# moire_v1_5-routed.net
KiCad netlist of a schematic drawn in EAGLE
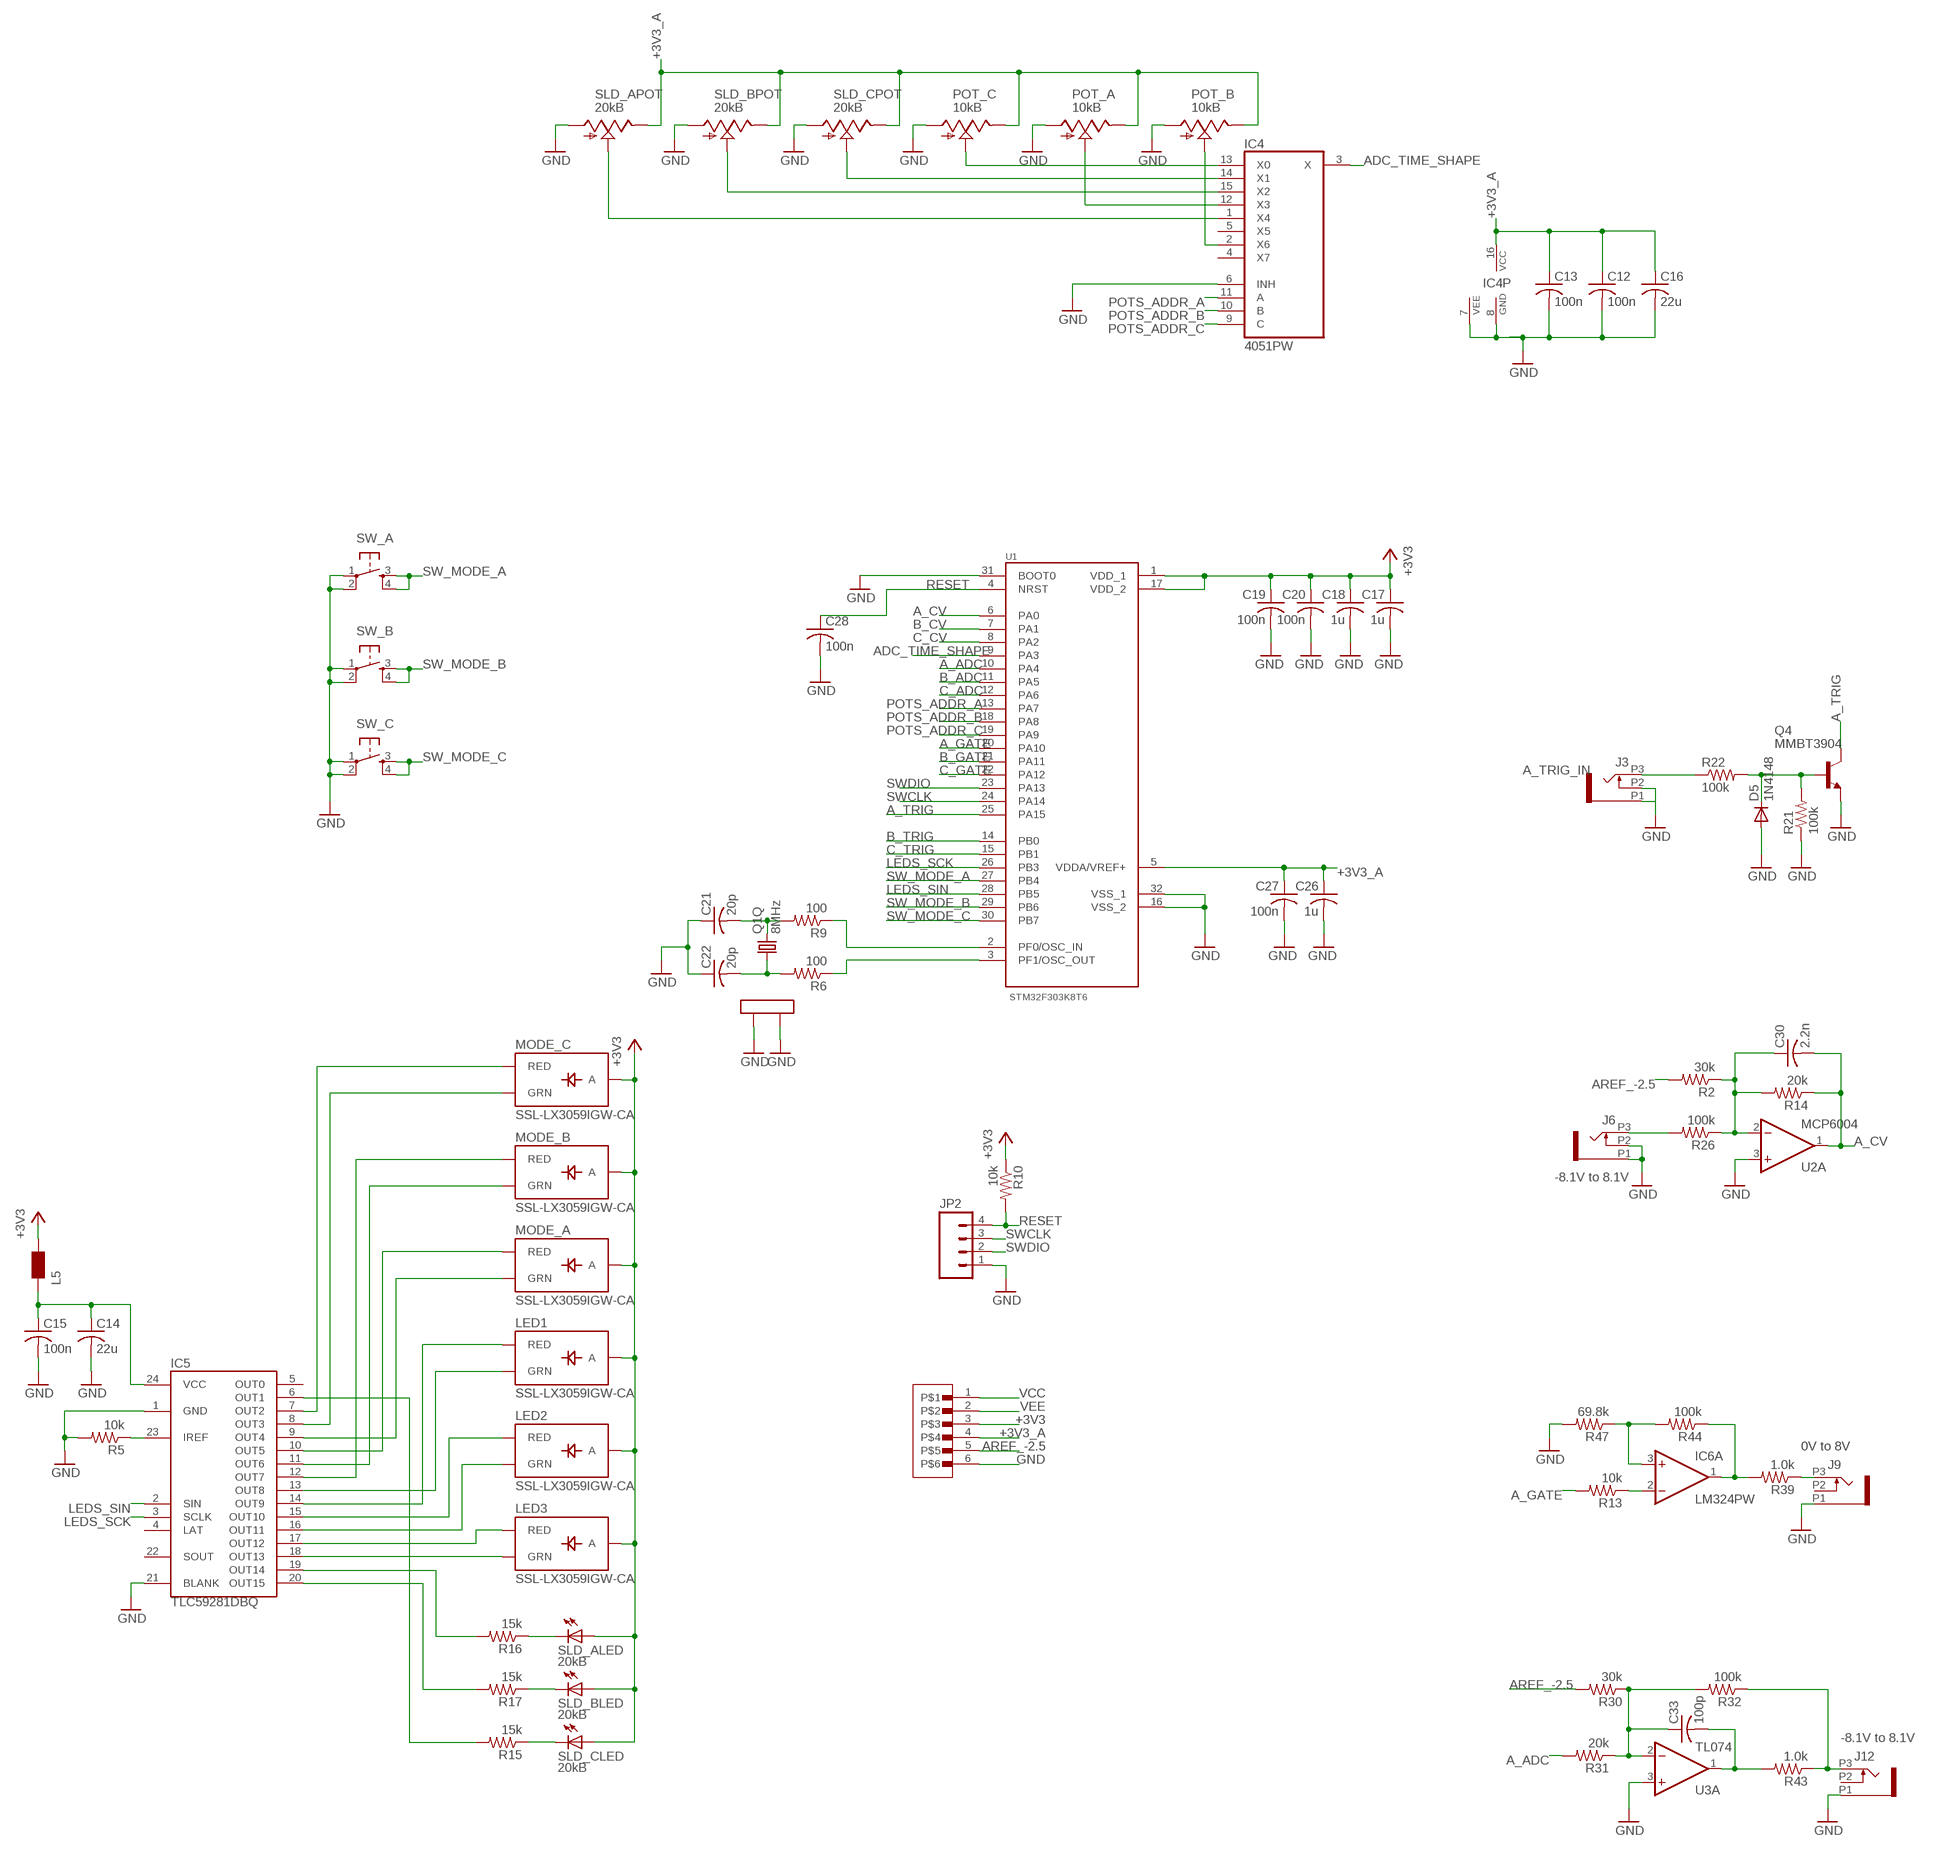
[diagram p0: schematic, sheet 1, part 1 of 2]
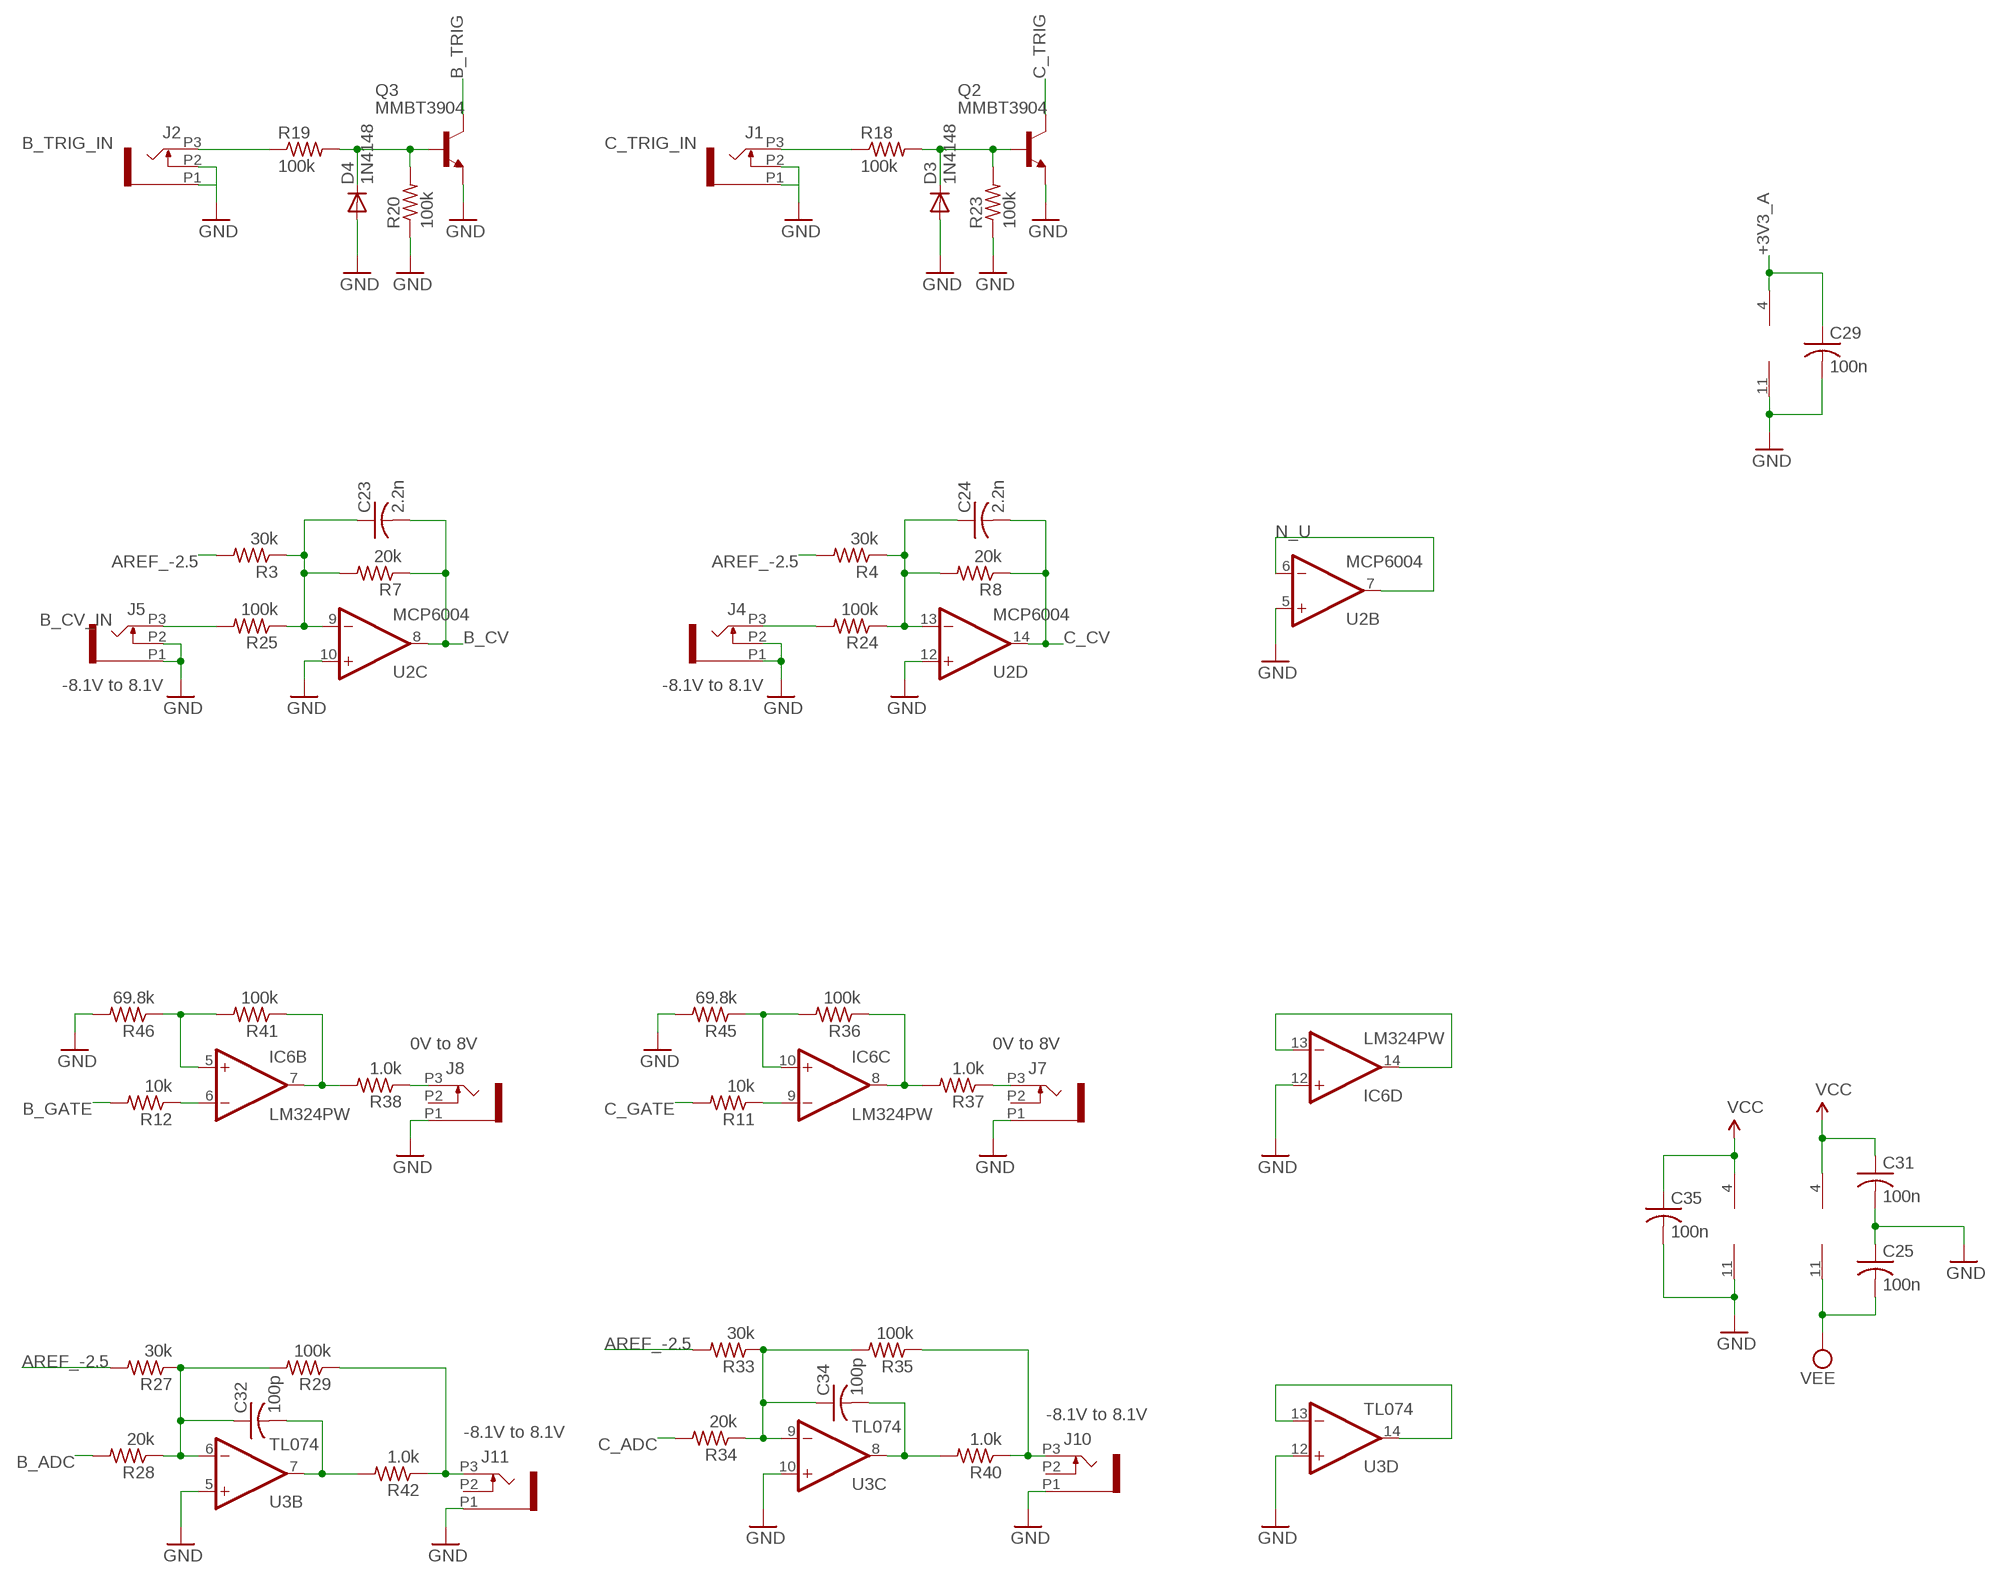
[diagram p1: schematic, sheet 1, part 2 of 2]
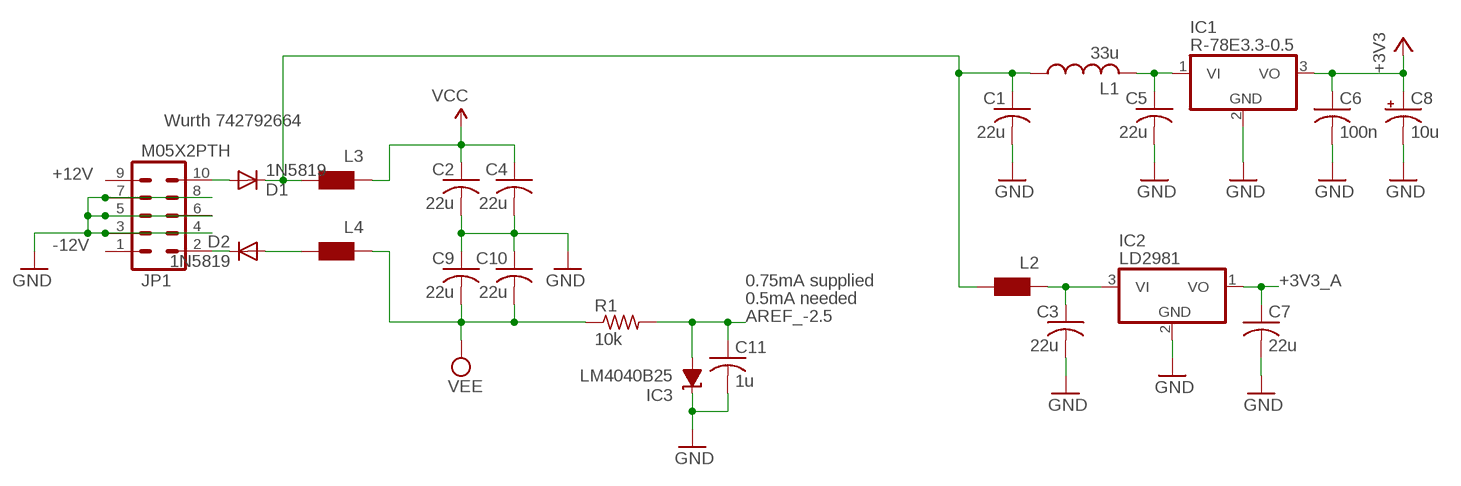
[diagram p2: schematic, sheet 2]

(export (version "E")
  (design (tool "Eeschema 10.0.6"))
  (components
    (comp (ref "C12")
      (value "100n")
      (footprint "eagle-import:C0603")
      (libsource (lib "eagle-import") (part "C-USC0603"))
    )
    (comp (ref "C13")
      (value "100n")
      (footprint "eagle-import:C0603")
      (libsource (lib "eagle-import") (part "C-USC0603"))
    )
    (comp (ref "C14")
      (value "22u")
      (footprint "eagle-import:C1206")
      (libsource (lib "eagle-import") (part "C-USC1206"))
    )
    (comp (ref "C15")
      (value "100n")
      (footprint "eagle-import:C0603")
      (libsource (lib "eagle-import") (part "C-USC0603"))
    )
    (comp (ref "C16")
      (value "22u")
      (footprint "eagle-import:C1206")
      (libsource (lib "eagle-import") (part "C-USC1206"))
    )
    (comp (ref "C17")
      (value "1u")
      (footprint "eagle-import:C0603")
      (libsource (lib "eagle-import") (part "C-USC0603"))
    )
    (comp (ref "C18")
      (value "1u")
      (footprint "eagle-import:C0603")
      (libsource (lib "eagle-import") (part "C-USC0603"))
    )
    (comp (ref "C19")
      (value "100n")
      (footprint "eagle-import:C0603")
      (libsource (lib "eagle-import") (part "C-USC0603"))
    )
    (comp (ref "C20")
      (value "100n")
      (footprint "eagle-import:C0603")
      (libsource (lib "eagle-import") (part "C-USC0603"))
    )
    (comp (ref "C21")
      (value "20p")
      (footprint "eagle-import:C0603")
      (libsource (lib "eagle-import") (part "C-USC0603"))
    )
    (comp (ref "C22")
      (value "20p")
      (footprint "eagle-import:C0603")
      (libsource (lib "eagle-import") (part "C-USC0603"))
    )
    (comp (ref "C23")
      (value "2.2n")
      (footprint "eagle-import:C0603")
      (libsource (lib "eagle-import") (part "C-USC0603"))
    )
    (comp (ref "C24")
      (value "2.2n")
      (footprint "eagle-import:C0603")
      (libsource (lib "eagle-import") (part "C-USC0603"))
    )
    (comp (ref "C25")
      (value "100n")
      (footprint "eagle-import:C0603")
      (libsource (lib "eagle-import") (part "C-USC0603"))
    )
    (comp (ref "C26")
      (value "1u")
      (footprint "eagle-import:C0603")
      (libsource (lib "eagle-import") (part "C-USC0603"))
    )
    (comp (ref "C27")
      (value "100n")
      (footprint "eagle-import:C0603")
      (libsource (lib "eagle-import") (part "C-USC0603"))
    )
    (comp (ref "C28")
      (value "100n")
      (footprint "eagle-import:C0603")
      (libsource (lib "eagle-import") (part "C-USC0603"))
    )
    (comp (ref "C29")
      (value "100n")
      (footprint "eagle-import:C0603")
      (libsource (lib "eagle-import") (part "C-USC0603"))
    )
    (comp (ref "C30")
      (value "2.2n")
      (footprint "eagle-import:C0603")
      (libsource (lib "eagle-import") (part "C-USC0603"))
    )
    (comp (ref "C31")
      (value "100n")
      (footprint "eagle-import:C0603")
      (libsource (lib "eagle-import") (part "C-USC0603"))
    )
    (comp (ref "C32")
      (value "100p")
      (footprint "eagle-import:C0603")
      (libsource (lib "eagle-import") (part "C-USC0603"))
    )
    (comp (ref "C33")
      (value "100p")
      (footprint "eagle-import:C0603")
      (libsource (lib "eagle-import") (part "C-USC0603"))
    )
    (comp (ref "C34")
      (value "100p")
      (footprint "eagle-import:C0603")
      (libsource (lib "eagle-import") (part "C-USC0603"))
    )
    (comp (ref "C35")
      (value "100n")
      (footprint "eagle-import:C0603")
      (libsource (lib "eagle-import") (part "C-USC0603"))
    )
    (comp (ref "D3")
      (value "1N4148")
      (footprint "eagle-import:SOD523")
      (libsource (lib "eagle-import") (part "DIODE-SOD523"))
    )
    (comp (ref "D4")
      (value "1N4148")
      (footprint "eagle-import:SOD523")
      (libsource (lib "eagle-import") (part "DIODE-SOD523"))
    )
    (comp (ref "D5")
      (value "1N4148")
      (footprint "eagle-import:SOD523")
      (libsource (lib "eagle-import") (part "DIODE-SOD523"))
    )
    (comp (ref "IC4")
      (value "4051PW")
      (footprint "eagle-import:TSSOP16_065")
      (libsource (lib "eagle-import") (part "4051PW"))
    )
    (comp (ref "IC5")
      (value "TLC59281DBQ")
      (footprint "eagle-import:TSSOP24_0635")
      (libsource (lib "eagle-import") (part "TLC59281DBQ"))
    )
    (comp (ref "IC6")
      (value "LM324PW")
      (footprint "eagle-import:TSSOP14_065")
      (libsource (lib "eagle-import") (part "TL074PW"))
    )
    (comp (ref "J1")
      (value "PJ301_THONKICONN6")
      (footprint "eagle-import:WQP_PJ_301M6")
      (libsource (lib "eagle-import") (part "PJ301_THONKICONN6"))
    )
    (comp (ref "J2")
      (value "PJ301_THONKICONN6")
      (footprint "eagle-import:WQP_PJ_301M6")
      (libsource (lib "eagle-import") (part "PJ301_THONKICONN6"))
    )
    (comp (ref "J3")
      (value "PJ301_THONKICONN6")
      (footprint "eagle-import:WQP_PJ_301M6")
      (libsource (lib "eagle-import") (part "PJ301_THONKICONN6"))
    )
    (comp (ref "J4")
      (value "PJ301_THONKICONN6")
      (footprint "eagle-import:WQP_PJ_301M6")
      (libsource (lib "eagle-import") (part "PJ301_THONKICONN6"))
    )
    (comp (ref "J5")
      (value "PJ301_THONKICONN6")
      (footprint "eagle-import:WQP_PJ_301M6")
      (libsource (lib "eagle-import") (part "PJ301_THONKICONN6"))
    )
    (comp (ref "J6")
      (value "PJ301_THONKICONN6")
      (footprint "eagle-import:WQP_PJ_301M6")
      (libsource (lib "eagle-import") (part "PJ301_THONKICONN6"))
    )
    (comp (ref "J7")
      (value "PJ301_THONKICONN6")
      (footprint "eagle-import:WQP_PJ_301M6")
      (libsource (lib "eagle-import") (part "PJ301_THONKICONN6"))
    )
    (comp (ref "J8")
      (value "PJ301_THONKICONN6")
      (footprint "eagle-import:WQP_PJ_301M6")
      (libsource (lib "eagle-import") (part "PJ301_THONKICONN6"))
    )
    (comp (ref "J9")
      (value "PJ301_THONKICONN6")
      (footprint "eagle-import:WQP_PJ_301M6")
      (libsource (lib "eagle-import") (part "PJ301_THONKICONN6"))
    )
    (comp (ref "J10")
      (value "PJ301_THONKICONN6")
      (footprint "eagle-import:WQP_PJ_301M6")
      (libsource (lib "eagle-import") (part "PJ301_THONKICONN6"))
    )
    (comp (ref "J11")
      (value "PJ301_THONKICONN6")
      (footprint "eagle-import:WQP_PJ_301M6")
      (libsource (lib "eagle-import") (part "PJ301_THONKICONN6"))
    )
    (comp (ref "J12")
      (value "PJ301_THONKICONN6")
      (footprint "eagle-import:WQP_PJ_301M6")
      (libsource (lib "eagle-import") (part "PJ301_THONKICONN6"))
    )
    (comp (ref "JP2")
      (value "M04PTH")
      (footprint "eagle-import:1X04")
      (libsource (lib "eagle-import") (part "M04PTH"))
    )
    (comp (ref "L5")
      (value "WE-CBF_0603")
      (footprint "eagle-import:0603")
      (libsource (lib "eagle-import") (part "WE-CBF_0603"))
    )
    (comp (ref "LED1")
      (value "SSL-LX3059IGW-CA")
      (footprint "eagle-import:LED-BICOLOR-THROUGHHOLE-LUMEX")
      (libsource (lib "eagle-import") (part "LED-BICOLOR-THROUGHHOLE-CA"))
    )
    (comp (ref "LED2")
      (value "SSL-LX3059IGW-CA")
      (footprint "eagle-import:LED-BICOLOR-THROUGHHOLE-LUMEX")
      (libsource (lib "eagle-import") (part "LED-BICOLOR-THROUGHHOLE-CA"))
    )
    (comp (ref "LED3")
      (value "SSL-LX3059IGW-CA")
      (footprint "eagle-import:LED-BICOLOR-THROUGHHOLE-LUMEX")
      (libsource (lib "eagle-import") (part "LED-BICOLOR-THROUGHHOLE-CA"))
    )
    (comp (ref "MODE_A")
      (value "SSL-LX3059IGW-CA")
      (footprint "eagle-import:LED-BICOLOR-THROUGHHOLE-LUMEX")
      (libsource (lib "eagle-import") (part "LED-BICOLOR-THROUGHHOLE-CA"))
    )
    (comp (ref "MODE_B")
      (value "SSL-LX3059IGW-CA")
      (footprint "eagle-import:LED-BICOLOR-THROUGHHOLE-LUMEX")
      (libsource (lib "eagle-import") (part "LED-BICOLOR-THROUGHHOLE-CA"))
    )
    (comp (ref "MODE_C")
      (value "SSL-LX3059IGW-CA")
      (footprint "eagle-import:LED-BICOLOR-THROUGHHOLE-LUMEX")
      (libsource (lib "eagle-import") (part "LED-BICOLOR-THROUGHHOLE-CA"))
    )
    (comp (ref "POT_A")
      (value "10kB")
      (footprint "eagle-import:ALPS_POT_VERTICAL")
      (libsource (lib "eagle-import") (part "POT_USVERTICAL"))
    )
    (comp (ref "POT_B")
      (value "10kB")
      (footprint "eagle-import:ALPS_POT_VERTICAL")
      (libsource (lib "eagle-import") (part "POT_USVERTICAL"))
    )
    (comp (ref "POT_C")
      (value "10kB")
      (footprint "eagle-import:ALPS_POT_VERTICAL")
      (libsource (lib "eagle-import") (part "POT_USVERTICAL"))
    )
    (comp (ref "Q1")
      (value "8MHz")
      (footprint "eagle-import:CTS406")
      (libsource (lib "eagle-import") (part "CRYSTAL"))
    )
    (comp (ref "Q2")
      (value "MMBT3904")
      (footprint "eagle-import:SOT23-BEC")
      (libsource (lib "eagle-import") (part "-NPN-SOT23-BECMMBT3904LT1"))
    )
    (comp (ref "Q3")
      (value "MMBT3904")
      (footprint "eagle-import:SOT23-BEC")
      (libsource (lib "eagle-import") (part "-NPN-SOT23-BECMMBT3904LT1"))
    )
    (comp (ref "Q4")
      (value "MMBT3904")
      (footprint "eagle-import:SOT23-BEC")
      (libsource (lib "eagle-import") (part "-NPN-SOT23-BECMMBT3904LT1"))
    )
    (comp (ref "R2")
      (value "30k")
      (footprint "eagle-import:R0603")
      (libsource (lib "eagle-import") (part "R-US_R0603"))
    )
    (comp (ref "R3")
      (value "30k")
      (footprint "eagle-import:R0603")
      (libsource (lib "eagle-import") (part "R-US_R0603"))
    )
    (comp (ref "R4")
      (value "30k")
      (footprint "eagle-import:R0603")
      (libsource (lib "eagle-import") (part "R-US_R0603"))
    )
    (comp (ref "R5")
      (value "10k")
      (footprint "eagle-import:R0603")
      (libsource (lib "eagle-import") (part "R-US_R0603"))
    )
    (comp (ref "R6")
      (value "100")
      (footprint "eagle-import:R0603")
      (libsource (lib "eagle-import") (part "R-US_R0603"))
    )
    (comp (ref "R7")
      (value "20k")
      (footprint "eagle-import:R0603")
      (libsource (lib "eagle-import") (part "R-US_R0603"))
    )
    (comp (ref "R8")
      (value "20k")
      (footprint "eagle-import:R0603")
      (libsource (lib "eagle-import") (part "R-US_R0603"))
    )
    (comp (ref "R9")
      (value "100")
      (footprint "eagle-import:R0603")
      (libsource (lib "eagle-import") (part "R-US_R0603"))
    )
    (comp (ref "R10")
      (value "10k")
      (footprint "eagle-import:R0603")
      (libsource (lib "eagle-import") (part "R-US_R0603"))
    )
    (comp (ref "R11")
      (value "10k")
      (footprint "eagle-import:R0603")
      (libsource (lib "eagle-import") (part "R-US_R0603"))
    )
    (comp (ref "R12")
      (value "10k")
      (footprint "eagle-import:R0603")
      (libsource (lib "eagle-import") (part "R-US_R0603"))
    )
    (comp (ref "R13")
      (value "10k")
      (footprint "eagle-import:R0603")
      (libsource (lib "eagle-import") (part "R-US_R0603"))
    )
    (comp (ref "R14")
      (value "20k")
      (footprint "eagle-import:R0603")
      (libsource (lib "eagle-import") (part "R-US_R0603"))
    )
    (comp (ref "R15")
      (value "15k")
      (footprint "eagle-import:R0603")
      (libsource (lib "eagle-import") (part "R-US_R0603"))
    )
    (comp (ref "R16")
      (value "15k")
      (footprint "eagle-import:R0603")
      (libsource (lib "eagle-import") (part "R-US_R0603"))
    )
    (comp (ref "R17")
      (value "15k")
      (footprint "eagle-import:R0603")
      (libsource (lib "eagle-import") (part "R-US_R0603"))
    )
    (comp (ref "R18")
      (value "100k")
      (footprint "eagle-import:R0603")
      (libsource (lib "eagle-import") (part "R-US_R0603"))
    )
    (comp (ref "R19")
      (value "100k")
      (footprint "eagle-import:R0603")
      (libsource (lib "eagle-import") (part "R-US_R0603"))
    )
    (comp (ref "R20")
      (value "100k")
      (footprint "eagle-import:R0603")
      (libsource (lib "eagle-import") (part "R-US_R0603"))
    )
    (comp (ref "R21")
      (value "100k")
      (footprint "eagle-import:R0603")
      (libsource (lib "eagle-import") (part "R-US_R0603"))
    )
    (comp (ref "R22")
      (value "100k")
      (footprint "eagle-import:R0603")
      (libsource (lib "eagle-import") (part "R-US_R0603"))
    )
    (comp (ref "R23")
      (value "100k")
      (footprint "eagle-import:R0603")
      (libsource (lib "eagle-import") (part "R-US_R0603"))
    )
    (comp (ref "R24")
      (value "100k")
      (footprint "eagle-import:R0603")
      (libsource (lib "eagle-import") (part "R-US_R0603"))
    )
    (comp (ref "R25")
      (value "100k")
      (footprint "eagle-import:R0603")
      (libsource (lib "eagle-import") (part "R-US_R0603"))
    )
    (comp (ref "R26")
      (value "100k")
      (footprint "eagle-import:R0603")
      (libsource (lib "eagle-import") (part "R-US_R0603"))
    )
    (comp (ref "R27")
      (value "30k")
      (footprint "eagle-import:R0603")
      (libsource (lib "eagle-import") (part "R-US_R0603"))
    )
    (comp (ref "R28")
      (value "20k")
      (footprint "eagle-import:R0603")
      (libsource (lib "eagle-import") (part "R-US_R0603"))
    )
    (comp (ref "R29")
      (value "100k")
      (footprint "eagle-import:R0603")
      (libsource (lib "eagle-import") (part "R-US_R0603"))
    )
    (comp (ref "R30")
      (value "30k")
      (footprint "eagle-import:R0603")
      (libsource (lib "eagle-import") (part "R-US_R0603"))
    )
    (comp (ref "R31")
      (value "20k")
      (footprint "eagle-import:R0603")
      (libsource (lib "eagle-import") (part "R-US_R0603"))
    )
    (comp (ref "R32")
      (value "100k")
      (footprint "eagle-import:R0603")
      (libsource (lib "eagle-import") (part "R-US_R0603"))
    )
    (comp (ref "R33")
      (value "30k")
      (footprint "eagle-import:R0603")
      (libsource (lib "eagle-import") (part "R-US_R0603"))
    )
    (comp (ref "R34")
      (value "20k")
      (footprint "eagle-import:R0603")
      (libsource (lib "eagle-import") (part "R-US_R0603"))
    )
    (comp (ref "R35")
      (value "100k")
      (footprint "eagle-import:R0603")
      (libsource (lib "eagle-import") (part "R-US_R0603"))
    )
    (comp (ref "R36")
      (value "100k")
      (footprint "eagle-import:R0603")
      (libsource (lib "eagle-import") (part "R-US_R0603"))
    )
    (comp (ref "R37")
      (value "1.0k")
      (footprint "eagle-import:R0603")
      (libsource (lib "eagle-import") (part "R-US_R0603"))
    )
    (comp (ref "R38")
      (value "1.0k")
      (footprint "eagle-import:R0603")
      (libsource (lib "eagle-import") (part "R-US_R0603"))
    )
    (comp (ref "R39")
      (value "1.0k")
      (footprint "eagle-import:R0603")
      (libsource (lib "eagle-import") (part "R-US_R0603"))
    )
    (comp (ref "R40")
      (value "1.0k")
      (footprint "eagle-import:R0603")
      (libsource (lib "eagle-import") (part "R-US_R0603"))
    )
    (comp (ref "R41")
      (value "100k")
      (footprint "eagle-import:R0603")
      (libsource (lib "eagle-import") (part "R-US_R0603"))
    )
    (comp (ref "R42")
      (value "1.0k")
      (footprint "eagle-import:R0603")
      (libsource (lib "eagle-import") (part "R-US_R0603"))
    )
    (comp (ref "R43")
      (value "1.0k")
      (footprint "eagle-import:R0603")
      (libsource (lib "eagle-import") (part "R-US_R0603"))
    )
    (comp (ref "R44")
      (value "100k")
      (footprint "eagle-import:R0603")
      (libsource (lib "eagle-import") (part "R-US_R0603"))
    )
    (comp (ref "R45")
      (value "69.8k")
      (footprint "eagle-import:R0603")
      (libsource (lib "eagle-import") (part "R-US_R0603"))
    )
    (comp (ref "R46")
      (value "69.8k")
      (footprint "eagle-import:R0603")
      (libsource (lib "eagle-import") (part "R-US_R0603"))
    )
    (comp (ref "R47")
      (value "69.8k")
      (footprint "eagle-import:R0603")
      (libsource (lib "eagle-import") (part "R-US_R0603"))
    )
    (comp (ref "SLD_A")
      (value "20kB")
      (footprint "eagle-import:BOURNS_SLIDER")
      (libsource (lib "eagle-import") (part "BOURNS_SLIDER"))
    )
    (comp (ref "SLD_B")
      (value "20kB")
      (footprint "eagle-import:BOURNS_SLIDER")
      (libsource (lib "eagle-import") (part "BOURNS_SLIDER"))
    )
    (comp (ref "SLD_C")
      (value "20kB")
      (footprint "eagle-import:BOURNS_SLIDER")
      (libsource (lib "eagle-import") (part "BOURNS_SLIDER"))
    )
    (comp (ref "SW_A")
      (value "TAC_SWITCHPTH")
      (footprint "eagle-import:TACTILE-PTH")
      (libsource (lib "eagle-import") (part "TAC_SWITCHPTH"))
    )
    (comp (ref "SW_B")
      (value "TAC_SWITCHPTH")
      (footprint "eagle-import:TACTILE-PTH")
      (libsource (lib "eagle-import") (part "TAC_SWITCHPTH"))
    )
    (comp (ref "SW_C")
      (value "TAC_SWITCHPTH")
      (footprint "eagle-import:TACTILE-PTH")
      (libsource (lib "eagle-import") (part "TAC_SWITCHPTH"))
    )
    (comp (ref "U$1")
      (value "1X6-SMD-TESTPAD")
      (footprint "eagle-import:6X1-SMD-TESTPAD")
      (libsource (lib "eagle-import") (part "1X6-SMD-TESTPAD"))
    )
    (comp (ref "U1")
      (value "STM32F303K8T6")
      (footprint "eagle-import:QFP80P900X900X160-32N")
      (fields (field (name "MF") "STMicroelectronics"))
      (libsource (lib "eagle-import") (part "STM32F303K8T6"))
    )
    (comp (ref "U2")
      (value "MCP6004")
      (footprint "eagle-import:SO14")
      (libsource (lib "eagle-import") (part "MCP6004_SMD"))
    )
    (comp (ref "U3")
      (value "TL074")
      (footprint "eagle-import:SO14")
      (libsource (lib "eagle-import") (part "TL074_SMD"))
    )
    (comp (ref "C1")
      (value "22u")
      (footprint "eagle-import:C1206")
      (libsource (lib "eagle-import") (part "C-USC1206"))
    )
    (comp (ref "C2")
      (value "22u")
      (footprint "eagle-import:C1206")
      (libsource (lib "eagle-import") (part "C-USC1206"))
    )
    (comp (ref "C3")
      (value "22u")
      (footprint "eagle-import:C1206")
      (libsource (lib "eagle-import") (part "C-USC1206"))
    )
    (comp (ref "C4")
      (value "22u")
      (footprint "eagle-import:C1206")
      (libsource (lib "eagle-import") (part "C-USC1206"))
    )
    (comp (ref "C5")
      (value "22u")
      (footprint "eagle-import:C1206")
      (libsource (lib "eagle-import") (part "C-USC1206"))
    )
    (comp (ref "C6")
      (value "100n")
      (footprint "eagle-import:C0603")
      (libsource (lib "eagle-import") (part "C-USC0603"))
    )
    (comp (ref "C7")
      (value "22u")
      (footprint "eagle-import:C1206")
      (libsource (lib "eagle-import") (part "C-USC1206"))
    )
    (comp (ref "C8")
      (value "10u")
      (footprint "eagle-import:PANASONIC_A")
      (libsource (lib "eagle-import") (part "CPOL-USA"))
    )
    (comp (ref "C9")
      (value "22u")
      (footprint "eagle-import:C1206")
      (libsource (lib "eagle-import") (part "C-USC1206"))
    )
    (comp (ref "C10")
      (value "22u")
      (footprint "eagle-import:C1206")
      (libsource (lib "eagle-import") (part "C-USC1206"))
    )
    (comp (ref "C11")
      (value "1u")
      (footprint "eagle-import:C0603")
      (libsource (lib "eagle-import") (part "C-USC0603"))
    )
    (comp (ref "D1")
      (value "1N5819")
      (footprint "eagle-import:SOD123")
      (libsource (lib "eagle-import") (part "DIODE-SOD123"))
    )
    (comp (ref "D2")
      (value "1N5819")
      (footprint "eagle-import:SOD123")
      (libsource (lib "eagle-import") (part "DIODE-SOD123"))
    )
    (comp (ref "IC1")
      (value "R-78E3.3-0.5")
      (footprint "eagle-import:WE78")
      (libsource (lib "eagle-import") (part "WE173950378"))
    )
    (comp (ref "IC2")
      (value "LD2981")
      (footprint "eagle-import:SOT89")
      (libsource (lib "eagle-import") (part "LD2981ABU"))
    )
    (comp (ref "IC3")
      (value "LM4040B25")
      (footprint "eagle-import:DBZ_R-PDSO-G3")
      (libsource (lib "eagle-import") (part "LM4041DBZB12"))
    )
    (comp (ref "JP1")
      (value "M05X2PTH")
      (footprint "eagle-import:2X5-PTH")
      (libsource (lib "eagle-import") (part "M05X2PTH"))
    )
    (comp (ref "L1")
      (value "33u")
      (footprint "eagle-import:L2012C")
      (libsource (lib "eagle-import") (part "L-USL2012C"))
    )
    (comp (ref "L2")
      (value "WE-CBF_0603")
      (footprint "eagle-import:0603")
      (libsource (lib "eagle-import") (part "WE-CBF_0603"))
    )
    (comp (ref "L3")
      (value "WE-CBF_0603")
      (footprint "eagle-import:0603")
      (libsource (lib "eagle-import") (part "WE-CBF_0603"))
    )
    (comp (ref "L4")
      (value "WE-CBF_0603")
      (footprint "eagle-import:0603")
      (libsource (lib "eagle-import") (part "WE-CBF_0603"))
    )
    (comp (ref "R1")
      (value "10k")
      (footprint "eagle-import:R0603")
      (libsource (lib "eagle-import") (part "R-US_R0603"))
    )
  )
  (nets
    (net (code "1") (name "+3V3") (class "Default")
      (node (ref "C17") (pin "1") (pinfunction "1_1") (pintype "passive"))
      (node (ref "C18") (pin "1") (pinfunction "1_1") (pintype "passive"))
      (node (ref "C19") (pin "1") (pinfunction "1_1") (pintype "passive"))
      (node (ref "C20") (pin "1") (pinfunction "1_1") (pintype "passive"))
      (node (ref "C6") (pin "1") (pinfunction "1_1") (pintype "passive"))
      (node (ref "C8") (pin "+") (pinfunction "+_+") (pintype "passive"))
      (node (ref "IC1") (pin "3") (pinfunction "VO_3") (pintype "passive"))
      (node (ref "L5") (pin "2") (pinfunction "2_2") (pintype "passive"))
      (node (ref "LED1") (pin "A") (pinfunction "A_A") (pintype "bidirectional"))
      (node (ref "LED2") (pin "A") (pinfunction "A_A") (pintype "bidirectional"))
      (node (ref "LED3") (pin "A") (pinfunction "A_A") (pintype "bidirectional"))
      (node (ref "MODE_A") (pin "A") (pinfunction "A_A") (pintype "bidirectional"))
      (node (ref "MODE_B") (pin "A") (pinfunction "A_A") (pintype "bidirectional"))
      (node (ref "MODE_C") (pin "A") (pinfunction "A_A") (pintype "bidirectional"))
      (node (ref "R10") (pin "1") (pinfunction "1_1") (pintype "passive"))
      (node (ref "SLD_A") (pin "B") (pinfunction "A_B") (pintype "passive"))
      (node (ref "SLD_B") (pin "B") (pinfunction "A_B") (pintype "passive"))
      (node (ref "SLD_C") (pin "B") (pinfunction "A_B") (pintype "passive"))
      (node (ref "U$1") (pin "3") (pinfunction "P$3_3") (pintype "bidirectional"))
      (node (ref "U1") (pin "1") (pinfunction "VDD_1_1") (pintype "power_in"))
      (node (ref "U1") (pin "17") (pinfunction "VDD_2_17") (pintype "power_in"))
    )
    (net (code "2") (name "+3V3_A") (class "Default")
      (node (ref "C12") (pin "1") (pinfunction "1_1") (pintype "passive"))
      (node (ref "C13") (pin "1") (pinfunction "1_1") (pintype "passive"))
      (node (ref "C16") (pin "1") (pinfunction "1_1") (pintype "passive"))
      (node (ref "C26") (pin "1") (pinfunction "1_1") (pintype "passive"))
      (node (ref "C27") (pin "1") (pinfunction "1_1") (pintype "passive"))
      (node (ref "C29") (pin "1") (pinfunction "1_1") (pintype "passive"))
      (node (ref "C7") (pin "1") (pinfunction "1_1") (pintype "passive"))
      (node (ref "IC2") (pin "1") (pinfunction "VO_1") (pintype "passive"))
      (node (ref "IC4") (pin "16") (pinfunction "VCC_16") (pintype "power_in"))
      (node (ref "POT_A") (pin "P$1") (pinfunction "E_P$1") (pintype "passive"))
      (node (ref "POT_B") (pin "P$1") (pinfunction "E_P$1") (pintype "passive"))
      (node (ref "POT_C") (pin "P$1") (pinfunction "E_P$1") (pintype "passive"))
      (node (ref "SLD_A") (pin "3") (pinfunction "E_3") (pintype "passive"))
      (node (ref "SLD_B") (pin "3") (pinfunction "E_3") (pintype "passive"))
      (node (ref "SLD_C") (pin "3") (pinfunction "E_3") (pintype "passive"))
      (node (ref "U$1") (pin "4") (pinfunction "P$4_4") (pintype "bidirectional"))
      (node (ref "U1") (pin "5") (pinfunction "VDDA/VREF+_5") (pintype "power_in"))
      (node (ref "U2") (pin "4") (pinfunction "V+_4") (pintype "power_in"))
    )
    (net (code "3") (name "+12V") (class "Default")
      (node (ref "D1") (pin "A") (pinfunction "A_A") (pintype "passive"))
      (node (ref "JP1") (pin "10") (pinfunction "10_10") (pintype "passive"))
      (node (ref "JP1") (pin "9") (pinfunction "9_9") (pintype "passive"))
    )
    (net (code "4") (name "-12V") (class "Default")
      (node (ref "D2") (pin "C") (pinfunction "C_C") (pintype "passive"))
      (node (ref "JP1") (pin "1") (pinfunction "1_1") (pintype "passive"))
      (node (ref "JP1") (pin "2") (pinfunction "2_2") (pintype "passive"))
    )
    (net (code "5") (name "ADC_TIME_SHAPE") (class "Default")
      (node (ref "IC4") (pin "3") (pinfunction "X_3") (pintype "bidirectional"))
      (node (ref "U1") (pin "9") (pinfunction "PA3_9") (pintype "bidirectional"))
    )
    (net (code "6") (name "AREF_-2.5") (class "Default")
      (node (ref "C11") (pin "1") (pinfunction "1_1") (pintype "passive"))
      (node (ref "IC3") (pin "2") (pinfunction "A_2") (pintype "passive"))
      (node (ref "R1") (pin "2") (pinfunction "2_2") (pintype "passive"))
      (node (ref "R2") (pin "2") (pinfunction "2_2") (pintype "passive"))
      (node (ref "R27") (pin "2") (pinfunction "2_2") (pintype "passive"))
      (node (ref "R3") (pin "2") (pinfunction "2_2") (pintype "passive"))
      (node (ref "R30") (pin "2") (pinfunction "2_2") (pintype "passive"))
      (node (ref "R33") (pin "2") (pinfunction "2_2") (pintype "passive"))
      (node (ref "R4") (pin "2") (pinfunction "2_2") (pintype "passive"))
      (node (ref "U$1") (pin "5") (pinfunction "P$5_5") (pintype "bidirectional"))
    )
    (net (code "7") (name "A_ADC") (class "Default")
      (node (ref "R31") (pin "2") (pinfunction "2_2") (pintype "passive"))
      (node (ref "U1") (pin "10") (pinfunction "PA4_10") (pintype "bidirectional"))
    )
    (net (code "8") (name "A_CV") (class "Default")
      (node (ref "C30") (pin "2") (pinfunction "2_2") (pintype "passive"))
      (node (ref "R14") (pin "1") (pinfunction "1_1") (pintype "passive"))
      (node (ref "U1") (pin "6") (pinfunction "PA0_6") (pintype "bidirectional"))
      (node (ref "U2") (pin "1") (pinfunction "OUT_1") (pintype "output"))
    )
    (net (code "9") (name "A_GATE") (class "Default")
      (node (ref "R13") (pin "2") (pinfunction "2_2") (pintype "passive"))
      (node (ref "U1") (pin "20") (pinfunction "PA10_20") (pintype "bidirectional"))
    )
    (net (code "10") (name "A_TRIG") (class "Default")
      (node (ref "Q4") (pin "C") (pinfunction "C_C") (pintype "passive"))
      (node (ref "U1") (pin "25") (pinfunction "PA15_25") (pintype "bidirectional"))
    )
    (net (code "11") (name "A_TRIG_IN") (class "Default")
      (node (ref "J3") (pin "P3") (pinfunction "3_P3") (pintype "passive"))
      (node (ref "R22") (pin "1") (pinfunction "1_1") (pintype "passive"))
    )
    (net (code "12") (name "B_ADC") (class "Default")
      (node (ref "R28") (pin "2") (pinfunction "2_2") (pintype "passive"))
      (node (ref "U1") (pin "11") (pinfunction "PA5_11") (pintype "bidirectional"))
    )
    (net (code "13") (name "B_CV") (class "Default")
      (node (ref "C23") (pin "2") (pinfunction "2_2") (pintype "passive"))
      (node (ref "R7") (pin "1") (pinfunction "1_1") (pintype "passive"))
      (node (ref "U1") (pin "7") (pinfunction "PA1_7") (pintype "bidirectional"))
      (node (ref "U2") (pin "8") (pinfunction "OUT_8") (pintype "output"))
    )
    (net (code "14") (name "B_CV_IN") (class "Default")
      (node (ref "J5") (pin "P3") (pinfunction "3_P3") (pintype "passive"))
      (node (ref "R25") (pin "2") (pinfunction "2_2") (pintype "passive"))
    )
    (net (code "15") (name "B_GATE") (class "Default")
      (node (ref "R12") (pin "2") (pinfunction "2_2") (pintype "passive"))
      (node (ref "U1") (pin "21") (pinfunction "PA11_21") (pintype "bidirectional"))
    )
    (net (code "16") (name "B_TRIG") (class "Default")
      (node (ref "Q3") (pin "C") (pinfunction "C_C") (pintype "passive"))
      (node (ref "U1") (pin "14") (pinfunction "PB0_14") (pintype "bidirectional"))
    )
    (net (code "17") (name "B_TRIG_IN") (class "Default")
      (node (ref "J2") (pin "P3") (pinfunction "3_P3") (pintype "passive"))
      (node (ref "R19") (pin "1") (pinfunction "1_1") (pintype "passive"))
    )
    (net (code "18") (name "C_ADC") (class "Default")
      (node (ref "R34") (pin "2") (pinfunction "2_2") (pintype "passive"))
      (node (ref "U1") (pin "12") (pinfunction "PA6_12") (pintype "bidirectional"))
    )
    (net (code "19") (name "C_CV") (class "Default")
      (node (ref "C24") (pin "2") (pinfunction "2_2") (pintype "passive"))
      (node (ref "R8") (pin "1") (pinfunction "1_1") (pintype "passive"))
      (node (ref "U1") (pin "8") (pinfunction "PA2_8") (pintype "bidirectional"))
      (node (ref "U2") (pin "14") (pinfunction "OUT_14") (pintype "output"))
    )
    (net (code "20") (name "C_GATE") (class "Default")
      (node (ref "R11") (pin "2") (pinfunction "2_2") (pintype "passive"))
      (node (ref "U1") (pin "22") (pinfunction "PA12_22") (pintype "bidirectional"))
    )
    (net (code "21") (name "C_TRIG") (class "Default")
      (node (ref "Q2") (pin "C") (pinfunction "C_C") (pintype "passive"))
      (node (ref "U1") (pin "15") (pinfunction "PB1_15") (pintype "bidirectional"))
    )
    (net (code "22") (name "C_TRIG_IN") (class "Default")
      (node (ref "J1") (pin "P3") (pinfunction "3_P3") (pintype "passive"))
      (node (ref "R18") (pin "1") (pinfunction "1_1") (pintype "passive"))
    )
    (net (code "23") (name "GND") (class "Default")
      (node (ref "C1") (pin "2") (pinfunction "2_2") (pintype "passive"))
      (node (ref "C10") (pin "1") (pinfunction "1_1") (pintype "passive"))
      (node (ref "C11") (pin "2") (pinfunction "2_2") (pintype "passive"))
      (node (ref "C12") (pin "2") (pinfunction "2_2") (pintype "passive"))
      (node (ref "C13") (pin "2") (pinfunction "2_2") (pintype "passive"))
      (node (ref "C14") (pin "2") (pinfunction "2_2") (pintype "passive"))
      (node (ref "C15") (pin "2") (pinfunction "2_2") (pintype "passive"))
      (node (ref "C16") (pin "2") (pinfunction "2_2") (pintype "passive"))
      (node (ref "C17") (pin "2") (pinfunction "2_2") (pintype "passive"))
      (node (ref "C18") (pin "2") (pinfunction "2_2") (pintype "passive"))
      (node (ref "C19") (pin "2") (pinfunction "2_2") (pintype "passive"))
      (node (ref "C2") (pin "2") (pinfunction "2_2") (pintype "passive"))
      (node (ref "C20") (pin "2") (pinfunction "2_2") (pintype "passive"))
      (node (ref "C21") (pin "1") (pinfunction "1_1") (pintype "passive"))
      (node (ref "C22") (pin "1") (pinfunction "1_1") (pintype "passive"))
      (node (ref "C25") (pin "1") (pinfunction "1_1") (pintype "passive"))
      (node (ref "C26") (pin "2") (pinfunction "2_2") (pintype "passive"))
      (node (ref "C27") (pin "2") (pinfunction "2_2") (pintype "passive"))
      (node (ref "C28") (pin "2") (pinfunction "2_2") (pintype "passive"))
      (node (ref "C29") (pin "2") (pinfunction "2_2") (pintype "passive"))
      (node (ref "C3") (pin "2") (pinfunction "2_2") (pintype "passive"))
      (node (ref "C31") (pin "2") (pinfunction "2_2") (pintype "passive"))
      (node (ref "C35") (pin "2") (pinfunction "2_2") (pintype "passive"))
      (node (ref "C4") (pin "2") (pinfunction "2_2") (pintype "passive"))
      (node (ref "C5") (pin "2") (pinfunction "2_2") (pintype "passive"))
      (node (ref "C6") (pin "2") (pinfunction "2_2") (pintype "passive"))
      (node (ref "C7") (pin "2") (pinfunction "2_2") (pintype "passive"))
      (node (ref "C8") (pin "-") (pinfunction "-_-") (pintype "passive"))
      (node (ref "C9") (pin "1") (pinfunction "1_1") (pintype "passive"))
      (node (ref "D3") (pin "A") (pinfunction "A_A") (pintype "passive"))
      (node (ref "D4") (pin "A") (pinfunction "A_A") (pintype "passive"))
      (node (ref "D5") (pin "A") (pinfunction "A_A") (pintype "passive"))
      (node (ref "IC1") (pin "2") (pinfunction "GND_2") (pintype "passive"))
      (node (ref "IC2") (pin "2") (pinfunction "GND_2") (pintype "passive"))
      (node (ref "IC3") (pin "1") (pinfunction "C_1") (pintype "passive"))
      (node (ref "IC4") (pin "6") (pinfunction "INH_6") (pintype "input"))
      (node (ref "IC4") (pin "7") (pinfunction "VEE_7") (pintype "power_in"))
      (node (ref "IC4") (pin "8") (pinfunction "GND_8") (pintype "power_in"))
      (node (ref "IC5") (pin "1") (pinfunction "GND_1") (pintype "bidirectional"))
      (node (ref "IC5") (pin "21") (pinfunction "BLANK_21") (pintype "bidirectional"))
      (node (ref "IC6") (pin "11") (pinfunction "V-_11") (pintype "power_in"))
      (node (ref "IC6") (pin "12") (pinfunction "+IN_12") (pintype "input"))
      (node (ref "J1") (pin "P1") (pinfunction "1_P1") (pintype "passive"))
      (node (ref "J1") (pin "P2") (pinfunction "2_P2") (pintype "passive"))
      (node (ref "J10") (pin "P1") (pinfunction "1_P1") (pintype "passive"))
      (node (ref "J11") (pin "P1") (pinfunction "1_P1") (pintype "passive"))
      (node (ref "J12") (pin "P1") (pinfunction "1_P1") (pintype "passive"))
      (node (ref "J2") (pin "P1") (pinfunction "1_P1") (pintype "passive"))
      (node (ref "J2") (pin "P2") (pinfunction "2_P2") (pintype "passive"))
      (node (ref "J3") (pin "P1") (pinfunction "1_P1") (pintype "passive"))
      (node (ref "J3") (pin "P2") (pinfunction "2_P2") (pintype "passive"))
      (node (ref "J4") (pin "P1") (pinfunction "1_P1") (pintype "passive"))
      (node (ref "J4") (pin "P2") (pinfunction "2_P2") (pintype "passive"))
      (node (ref "J5") (pin "P1") (pinfunction "1_P1") (pintype "passive"))
      (node (ref "J5") (pin "P2") (pinfunction "2_P2") (pintype "passive"))
      (node (ref "J6") (pin "P1") (pinfunction "1_P1") (pintype "passive"))
      (node (ref "J6") (pin "P2") (pinfunction "2_P2") (pintype "passive"))
      (node (ref "J7") (pin "P1") (pinfunction "1_P1") (pintype "passive"))
      (node (ref "J8") (pin "P1") (pinfunction "1_P1") (pintype "passive"))
      (node (ref "J9") (pin "P1") (pinfunction "1_P1") (pintype "passive"))
      (node (ref "JP1") (pin "3") (pinfunction "3_3") (pintype "passive"))
      (node (ref "JP1") (pin "4") (pinfunction "4_4") (pintype "passive"))
      (node (ref "JP1") (pin "5") (pinfunction "5_5") (pintype "passive"))
      (node (ref "JP1") (pin "6") (pinfunction "6_6") (pintype "passive"))
      (node (ref "JP1") (pin "7") (pinfunction "7_7") (pintype "passive"))
      (node (ref "JP1") (pin "8") (pinfunction "8_8") (pintype "passive"))
      (node (ref "JP2") (pin "1") (pinfunction "1_1") (pintype "passive"))
      (node (ref "POT_A") (pin "P$3") (pinfunction "A_P$3") (pintype "passive"))
      (node (ref "POT_B") (pin "P$3") (pinfunction "A_P$3") (pintype "passive"))
      (node (ref "POT_C") (pin "P$3") (pinfunction "A_P$3") (pintype "passive"))
      (node (ref "Q1") (pin "2") (pinfunction "LID1_2") (pintype "power_in"))
      (node (ref "Q1") (pin "4") (pinfunction "LID2_4") (pintype "power_in"))
      (node (ref "Q2") (pin "E") (pinfunction "E_E") (pintype "passive"))
      (node (ref "Q3") (pin "E") (pinfunction "E_E") (pintype "passive"))
      (node (ref "Q4") (pin "E") (pinfunction "E_E") (pintype "passive"))
      (node (ref "R20") (pin "1") (pinfunction "1_1") (pintype "passive"))
      (node (ref "R21") (pin "1") (pinfunction "1_1") (pintype "passive"))
      (node (ref "R23") (pin "1") (pinfunction "1_1") (pintype "passive"))
      (node (ref "R45") (pin "2") (pinfunction "2_2") (pintype "passive"))
      (node (ref "R46") (pin "2") (pinfunction "2_2") (pintype "passive"))
      (node (ref "R47") (pin "2") (pinfunction "2_2") (pintype "passive"))
      (node (ref "R5") (pin "2") (pinfunction "2_2") (pintype "passive"))
      (node (ref "SLD_A") (pin "1") (pinfunction "A_1") (pintype "passive"))
      (node (ref "SLD_B") (pin "1") (pinfunction "A_1") (pintype "passive"))
      (node (ref "SLD_C") (pin "1") (pinfunction "A_1") (pintype "passive"))
      (node (ref "SW_A") (pin "1") (pinfunction "1_1") (pintype "passive"))
      (node (ref "SW_A") (pin "2") (pinfunction "2_2") (pintype "passive"))
      (node (ref "SW_B") (pin "1") (pinfunction "1_1") (pintype "passive"))
      (node (ref "SW_B") (pin "2") (pinfunction "2_2") (pintype "passive"))
      (node (ref "SW_C") (pin "1") (pinfunction "1_1") (pintype "passive"))
      (node (ref "SW_C") (pin "2") (pinfunction "2_2") (pintype "passive"))
      (node (ref "U$1") (pin "6") (pinfunction "P$6_6") (pintype "bidirectional"))
      (node (ref "U1") (pin "16") (pinfunction "VSS_2_16") (pintype "power_in"))
      (node (ref "U1") (pin "31") (pinfunction "BOOT0_31") (pintype "input"))
      (node (ref "U1") (pin "32") (pinfunction "VSS_1_32") (pintype "power_in"))
      (node (ref "U2") (pin "10") (pinfunction "+IN_10") (pintype "input"))
      (node (ref "U2") (pin "11") (pinfunction "V-_11") (pintype "power_in"))
      (node (ref "U2") (pin "12") (pinfunction "+IN_12") (pintype "input"))
      (node (ref "U2") (pin "3") (pinfunction "+IN_3") (pintype "input"))
      (node (ref "U2") (pin "5") (pinfunction "+IN_5") (pintype "input"))
      (node (ref "U3") (pin "10") (pinfunction "+IN_10") (pintype "input"))
      (node (ref "U3") (pin "12") (pinfunction "+IN_12") (pintype "input"))
      (node (ref "U3") (pin "3") (pinfunction "+IN_3") (pintype "input"))
      (node (ref "U3") (pin "5") (pinfunction "+IN_5") (pintype "input"))
    )
    (net (code "24") (name "LEDS_SCK") (class "Default")
      (node (ref "IC5") (pin "3") (pinfunction "SCLK_3") (pintype "bidirectional"))
      (node (ref "U1") (pin "26") (pinfunction "PB3_26") (pintype "bidirectional"))
    )
    (net (code "25") (name "LEDS_SIN") (class "Default")
      (node (ref "IC5") (pin "2") (pinfunction "SIN_2") (pintype "bidirectional"))
      (node (ref "U1") (pin "28") (pinfunction "PB5_28") (pintype "bidirectional"))
    )
    (net (code "26") (name "N_U") (class "Default")
      (node (ref "U2") (pin "6") (pinfunction "-IN_6") (pintype "input"))
      (node (ref "U2") (pin "7") (pinfunction "OUT_7") (pintype "output"))
    )
    (net (code "27") (name "Net-(C1-Pad1)") (class "Default")
      (node (ref "C1") (pin "1") (pinfunction "1_1") (pintype "passive"))
      (node (ref "D1") (pin "C") (pinfunction "C_C") (pintype "passive"))
      (node (ref "L1") (pin "1") (pinfunction "1_1") (pintype "passive"))
      (node (ref "L2") (pin "2") (pinfunction "2_2") (pintype "passive"))
      (node (ref "L3") (pin "2") (pinfunction "2_2") (pintype "passive"))
    )
    (net (code "28") (name "Net-(C22-Pad2)") (class "Default")
      (node (ref "C22") (pin "2") (pinfunction "2_2") (pintype "passive"))
      (node (ref "Q1") (pin "1") (pinfunction "1_1") (pintype "passive"))
      (node (ref "R6") (pin "2") (pinfunction "2_2") (pintype "passive"))
    )
    (net (code "29") (name "Net-(D2-PadA)") (class "Default")
      (node (ref "D2") (pin "A") (pinfunction "A_A") (pintype "passive"))
      (node (ref "L4") (pin "2") (pinfunction "2_2") (pintype "passive"))
    )
    (net (code "30") (name "Net-(D3-PadC)") (class "Default")
      (node (ref "D3") (pin "C") (pinfunction "C_C") (pintype "passive"))
      (node (ref "Q2") (pin "B") (pinfunction "B_B") (pintype "passive"))
      (node (ref "R18") (pin "2") (pinfunction "2_2") (pintype "passive"))
      (node (ref "R23") (pin "2") (pinfunction "2_2") (pintype "passive"))
    )
    (net (code "31") (name "Net-(D4-PadC)") (class "Default")
      (node (ref "D4") (pin "C") (pinfunction "C_C") (pintype "passive"))
      (node (ref "Q3") (pin "B") (pinfunction "B_B") (pintype "passive"))
      (node (ref "R19") (pin "2") (pinfunction "2_2") (pintype "passive"))
      (node (ref "R20") (pin "2") (pinfunction "2_2") (pintype "passive"))
    )
    (net (code "32") (name "Net-(D5-PadC)") (class "Default")
      (node (ref "D5") (pin "C") (pinfunction "C_C") (pintype "passive"))
      (node (ref "Q4") (pin "B") (pinfunction "B_B") (pintype "passive"))
      (node (ref "R21") (pin "2") (pinfunction "2_2") (pintype "passive"))
      (node (ref "R22") (pin "2") (pinfunction "2_2") (pintype "passive"))
    )
    (net (code "33") (name "Net-(IC1-VI)") (class "Default")
      (node (ref "C5") (pin "1") (pinfunction "1_1") (pintype "passive"))
      (node (ref "IC1") (pin "1") (pinfunction "VI_1") (pintype "input"))
      (node (ref "L1") (pin "2") (pinfunction "2_2") (pintype "passive"))
    )
    (net (code "34") (name "Net-(IC2-VI)") (class "Default")
      (node (ref "C3") (pin "1") (pinfunction "1_1") (pintype "passive"))
      (node (ref "IC2") (pin "3") (pinfunction "VI_3") (pintype "input"))
      (node (ref "L2") (pin "1") (pinfunction "1_1") (pintype "passive"))
    )
    (net (code "35") (name "Net-(IC4A-X0)") (class "Default")
      (node (ref "IC4") (pin "13") (pinfunction "X0_13") (pintype "bidirectional"))
      (node (ref "POT_C") (pin "P$2") (pinfunction "S_P$2") (pintype "passive"))
    )
    (net (code "36") (name "Net-(IC4A-X1)") (class "Default")
      (node (ref "IC4") (pin "14") (pinfunction "X1_14") (pintype "bidirectional"))
      (node (ref "SLD_C") (pin "2") (pinfunction "S_2") (pintype "passive"))
    )
    (net (code "37") (name "Net-(IC4A-X2)") (class "Default")
      (node (ref "IC4") (pin "15") (pinfunction "X2_15") (pintype "bidirectional"))
      (node (ref "SLD_B") (pin "2") (pinfunction "S_2") (pintype "passive"))
    )
    (net (code "38") (name "Net-(IC4A-X3)") (class "Default")
      (node (ref "IC4") (pin "12") (pinfunction "X3_12") (pintype "bidirectional"))
      (node (ref "POT_A") (pin "P$2") (pinfunction "S_P$2") (pintype "passive"))
    )
    (net (code "39") (name "Net-(IC4A-X4)") (class "Default")
      (node (ref "IC4") (pin "1") (pinfunction "X4_1") (pintype "bidirectional"))
      (node (ref "SLD_A") (pin "2") (pinfunction "S_2") (pintype "passive"))
    )
    (net (code "40") (name "Net-(IC4A-X6)") (class "Default")
      (node (ref "IC4") (pin "2") (pinfunction "X6_2") (pintype "bidirectional"))
      (node (ref "POT_B") (pin "P$2") (pinfunction "S_P$2") (pintype "passive"))
    )
    (net (code "41") (name "Net-(IC5-IREF)") (class "Default")
      (node (ref "IC5") (pin "23") (pinfunction "IREF_23") (pintype "bidirectional"))
      (node (ref "R5") (pin "1") (pinfunction "1_1") (pintype "passive"))
    )
    (net (code "42") (name "Net-(IC5-OUT1)") (class "Default")
      (node (ref "IC5") (pin "6") (pinfunction "OUT1_6") (pintype "bidirectional"))
      (node (ref "R15") (pin "2") (pinfunction "2_2") (pintype "passive"))
    )
    (net (code "43") (name "Net-(IC5-OUT2)") (class "Default")
      (node (ref "IC5") (pin "7") (pinfunction "OUT2_7") (pintype "bidirectional"))
      (node (ref "MODE_C") (pin "RED_C") (pinfunction "RED_RED_C") (pintype "bidirectional"))
    )
    (net (code "44") (name "Net-(IC5-OUT3)") (class "Default")
      (node (ref "IC5") (pin "8") (pinfunction "OUT3_8") (pintype "bidirectional"))
      (node (ref "MODE_C") (pin "GREEN_C") (pinfunction "GRN_GREEN_C") (pintype "bidirectional"))
    )
    (net (code "45") (name "Net-(IC5-OUT4)") (class "Default")
      (node (ref "IC5") (pin "9") (pinfunction "OUT4_9") (pintype "bidirectional"))
      (node (ref "MODE_A") (pin "GREEN_C") (pinfunction "GRN_GREEN_C") (pintype "bidirectional"))
    )
    (net (code "46") (name "Net-(IC5-OUT5)") (class "Default")
      (node (ref "IC5") (pin "10") (pinfunction "OUT5_10") (pintype "bidirectional"))
      (node (ref "MODE_A") (pin "RED_C") (pinfunction "RED_RED_C") (pintype "bidirectional"))
    )
    (net (code "47") (name "Net-(IC5-OUT6)") (class "Default")
      (node (ref "IC5") (pin "11") (pinfunction "OUT6_11") (pintype "bidirectional"))
      (node (ref "MODE_B") (pin "GREEN_C") (pinfunction "GRN_GREEN_C") (pintype "bidirectional"))
    )
    (net (code "48") (name "Net-(IC5-OUT7)") (class "Default")
      (node (ref "IC5") (pin "12") (pinfunction "OUT7_12") (pintype "bidirectional"))
      (node (ref "MODE_B") (pin "RED_C") (pinfunction "RED_RED_C") (pintype "bidirectional"))
    )
    (net (code "49") (name "Net-(IC5-OUT8)") (class "Default")
      (node (ref "IC5") (pin "13") (pinfunction "OUT8_13") (pintype "bidirectional"))
      (node (ref "LED1") (pin "GREEN_C") (pinfunction "GRN_GREEN_C") (pintype "bidirectional"))
    )
    (net (code "50") (name "Net-(IC5-OUT9)") (class "Default")
      (node (ref "IC5") (pin "14") (pinfunction "OUT9_14") (pintype "bidirectional"))
      (node (ref "LED1") (pin "RED_C") (pinfunction "RED_RED_C") (pintype "bidirectional"))
    )
    (net (code "51") (name "Net-(IC5-OUT10)") (class "Default")
      (node (ref "IC5") (pin "15") (pinfunction "OUT10_15") (pintype "bidirectional"))
      (node (ref "LED2") (pin "RED_C") (pinfunction "RED_RED_C") (pintype "bidirectional"))
    )
    (net (code "52") (name "Net-(IC5-OUT11)") (class "Default")
      (node (ref "IC5") (pin "16") (pinfunction "OUT11_16") (pintype "bidirectional"))
      (node (ref "LED2") (pin "GREEN_C") (pinfunction "GRN_GREEN_C") (pintype "bidirectional"))
    )
    (net (code "53") (name "Net-(IC5-OUT12)") (class "Default")
      (node (ref "IC5") (pin "17") (pinfunction "OUT12_17") (pintype "bidirectional"))
      (node (ref "LED3") (pin "RED_C") (pinfunction "RED_RED_C") (pintype "bidirectional"))
    )
    (net (code "54") (name "Net-(IC5-OUT13)") (class "Default")
      (node (ref "IC5") (pin "18") (pinfunction "OUT13_18") (pintype "bidirectional"))
      (node (ref "LED3") (pin "GREEN_C") (pinfunction "GRN_GREEN_C") (pintype "bidirectional"))
    )
    (net (code "55") (name "Net-(IC5-OUT14)") (class "Default")
      (node (ref "IC5") (pin "19") (pinfunction "OUT14_19") (pintype "bidirectional"))
      (node (ref "R16") (pin "2") (pinfunction "2_2") (pintype "passive"))
    )
    (net (code "56") (name "Net-(IC5-OUT15)") (class "Default")
      (node (ref "IC5") (pin "20") (pinfunction "OUT15_20") (pintype "bidirectional"))
      (node (ref "R17") (pin "2") (pinfunction "2_2") (pintype "passive"))
    )
    (net (code "57") (name "Net-(IC5-VCC)") (class "Default")
      (node (ref "C14") (pin "1") (pinfunction "1_1") (pintype "passive"))
      (node (ref "C15") (pin "1") (pinfunction "1_1") (pintype "passive"))
      (node (ref "IC5") (pin "24") (pinfunction "VCC_24") (pintype "bidirectional"))
      (node (ref "L5") (pin "1") (pinfunction "1_1") (pintype "passive"))
    )
    (net (code "58") (name "Net-(IC6A-+IN)") (class "Default")
      (node (ref "IC6") (pin "3") (pinfunction "+IN_3") (pintype "input"))
      (node (ref "R44") (pin "2") (pinfunction "2_2") (pintype "passive"))
      (node (ref "R47") (pin "1") (pinfunction "1_1") (pintype "passive"))
    )
    (net (code "59") (name "Net-(IC6A--IN)") (class "Default")
      (node (ref "IC6") (pin "2") (pinfunction "-IN_2") (pintype "input"))
      (node (ref "R13") (pin "1") (pinfunction "1_1") (pintype "passive"))
    )
    (net (code "60") (name "Net-(IC6A-OUT)") (class "Default")
      (node (ref "IC6") (pin "1") (pinfunction "OUT_1") (pintype "output"))
      (node (ref "R39") (pin "2") (pinfunction "2_2") (pintype "passive"))
      (node (ref "R44") (pin "1") (pinfunction "1_1") (pintype "passive"))
    )
    (net (code "61") (name "Net-(IC6B-+IN)") (class "Default")
      (node (ref "IC6") (pin "5") (pinfunction "+IN_5") (pintype "input"))
      (node (ref "R41") (pin "2") (pinfunction "2_2") (pintype "passive"))
      (node (ref "R46") (pin "1") (pinfunction "1_1") (pintype "passive"))
    )
    (net (code "62") (name "Net-(IC6B--IN)") (class "Default")
      (node (ref "IC6") (pin "6") (pinfunction "-IN_6") (pintype "input"))
      (node (ref "R12") (pin "1") (pinfunction "1_1") (pintype "passive"))
    )
    (net (code "63") (name "Net-(IC6B-OUT)") (class "Default")
      (node (ref "IC6") (pin "7") (pinfunction "OUT_7") (pintype "output"))
      (node (ref "R38") (pin "2") (pinfunction "2_2") (pintype "passive"))
      (node (ref "R41") (pin "1") (pinfunction "1_1") (pintype "passive"))
    )
    (net (code "64") (name "Net-(IC6C-+IN)") (class "Default")
      (node (ref "IC6") (pin "10") (pinfunction "+IN_10") (pintype "input"))
      (node (ref "R36") (pin "2") (pinfunction "2_2") (pintype "passive"))
      (node (ref "R45") (pin "1") (pinfunction "1_1") (pintype "passive"))
    )
    (net (code "65") (name "Net-(IC6C--IN)") (class "Default")
      (node (ref "IC6") (pin "9") (pinfunction "-IN_9") (pintype "input"))
      (node (ref "R11") (pin "1") (pinfunction "1_1") (pintype "passive"))
    )
    (net (code "66") (name "Net-(IC6C-OUT)") (class "Default")
      (node (ref "IC6") (pin "8") (pinfunction "OUT_8") (pintype "output"))
      (node (ref "R36") (pin "1") (pinfunction "1_1") (pintype "passive"))
      (node (ref "R37") (pin "2") (pinfunction "2_2") (pintype "passive"))
    )
    (net (code "67") (name "Net-(IC6D--IN)") (class "Default")
      (node (ref "IC6") (pin "13") (pinfunction "-IN_13") (pintype "input"))
      (node (ref "IC6") (pin "14") (pinfunction "OUT_14") (pintype "output"))
    )
    (net (code "68") (name "Net-(J4-3)") (class "Default")
      (node (ref "J4") (pin "P3") (pinfunction "3_P3") (pintype "passive"))
      (node (ref "R24") (pin "2") (pinfunction "2_2") (pintype "passive"))
    )
    (net (code "69") (name "Net-(J6-3)") (class "Default")
      (node (ref "J6") (pin "P3") (pinfunction "3_P3") (pintype "passive"))
      (node (ref "R26") (pin "2") (pinfunction "2_2") (pintype "passive"))
    )
    (net (code "70") (name "Net-(J7-3)") (class "Default")
      (node (ref "J7") (pin "P3") (pinfunction "3_P3") (pintype "passive"))
      (node (ref "R37") (pin "1") (pinfunction "1_1") (pintype "passive"))
    )
    (net (code "71") (name "Net-(J8-3)") (class "Default")
      (node (ref "J8") (pin "P3") (pinfunction "3_P3") (pintype "passive"))
      (node (ref "R38") (pin "1") (pinfunction "1_1") (pintype "passive"))
    )
    (net (code "72") (name "Net-(J9-3)") (class "Default")
      (node (ref "J9") (pin "P3") (pinfunction "3_P3") (pintype "passive"))
      (node (ref "R39") (pin "1") (pinfunction "1_1") (pintype "passive"))
    )
    (net (code "73") (name "Net-(J10-3)") (class "Default")
      (node (ref "J10") (pin "P3") (pinfunction "3_P3") (pintype "passive"))
      (node (ref "R35") (pin "1") (pinfunction "1_1") (pintype "passive"))
      (node (ref "R40") (pin "1") (pinfunction "1_1") (pintype "passive"))
    )
    (net (code "74") (name "Net-(J11-3)") (class "Default")
      (node (ref "J11") (pin "P3") (pinfunction "3_P3") (pintype "passive"))
      (node (ref "R29") (pin "1") (pinfunction "1_1") (pintype "passive"))
      (node (ref "R42") (pin "1") (pinfunction "1_1") (pintype "passive"))
    )
    (net (code "75") (name "Net-(J12-3)") (class "Default")
      (node (ref "J12") (pin "P3") (pinfunction "3_P3") (pintype "passive"))
      (node (ref "R32") (pin "1") (pinfunction "1_1") (pintype "passive"))
      (node (ref "R43") (pin "1") (pinfunction "1_1") (pintype "passive"))
    )
    (net (code "76") (name "Net-(Q1B-2)") (class "Default")
      (node (ref "C21") (pin "2") (pinfunction "2_2") (pintype "passive"))
      (node (ref "Q1") (pin "3") (pinfunction "2_3") (pintype "passive"))
      (node (ref "R9") (pin "2") (pinfunction "2_2") (pintype "passive"))
    )
    (net (code "77") (name "Net-(SLD_AA-C)") (class "Default")
      (node (ref "R16") (pin "1") (pinfunction "1_1") (pintype "passive"))
      (node (ref "SLD_A") (pin "E") (pinfunction "C_E") (pintype "passive"))
    )
    (net (code "78") (name "Net-(SLD_BA-C)") (class "Default")
      (node (ref "R17") (pin "1") (pinfunction "1_1") (pintype "passive"))
      (node (ref "SLD_B") (pin "E") (pinfunction "C_E") (pintype "passive"))
    )
    (net (code "79") (name "Net-(SLD_CA-C)") (class "Default")
      (node (ref "R15") (pin "1") (pinfunction "1_1") (pintype "passive"))
      (node (ref "SLD_C") (pin "E") (pinfunction "C_E") (pintype "passive"))
    )
    (net (code "80") (name "Net-(U1-PF0{slash}OSC_IN)") (class "Default")
      (node (ref "R9") (pin "1") (pinfunction "1_1") (pintype "passive"))
      (node (ref "U1") (pin "2") (pinfunction "PF0/OSC_IN_2") (pintype "bidirectional"))
    )
    (net (code "81") (name "Net-(U1-PF1{slash}OSC_OUT)") (class "Default")
      (node (ref "R6") (pin "1") (pinfunction "1_1") (pintype "passive"))
      (node (ref "U1") (pin "3") (pinfunction "PF1/OSC_OUT_3") (pintype "bidirectional"))
    )
    (net (code "82") (name "Net-(U2A--IN)") (class "Default")
      (node (ref "C30") (pin "1") (pinfunction "1_1") (pintype "passive"))
      (node (ref "R14") (pin "2") (pinfunction "2_2") (pintype "passive"))
      (node (ref "R2") (pin "1") (pinfunction "1_1") (pintype "passive"))
      (node (ref "R26") (pin "1") (pinfunction "1_1") (pintype "passive"))
      (node (ref "U2") (pin "2") (pinfunction "-IN_2") (pintype "input"))
    )
    (net (code "83") (name "Net-(U2C--IN)") (class "Default")
      (node (ref "C23") (pin "1") (pinfunction "1_1") (pintype "passive"))
      (node (ref "R25") (pin "1") (pinfunction "1_1") (pintype "passive"))
      (node (ref "R3") (pin "1") (pinfunction "1_1") (pintype "passive"))
      (node (ref "R7") (pin "2") (pinfunction "2_2") (pintype "passive"))
      (node (ref "U2") (pin "9") (pinfunction "-IN_9") (pintype "input"))
    )
    (net (code "84") (name "Net-(U2D--IN)") (class "Default")
      (node (ref "C24") (pin "1") (pinfunction "1_1") (pintype "passive"))
      (node (ref "R24") (pin "1") (pinfunction "1_1") (pintype "passive"))
      (node (ref "R4") (pin "1") (pinfunction "1_1") (pintype "passive"))
      (node (ref "R8") (pin "2") (pinfunction "2_2") (pintype "passive"))
      (node (ref "U2") (pin "13") (pinfunction "-IN_13") (pintype "input"))
    )
    (net (code "85") (name "Net-(U3A--IN)") (class "Default")
      (node (ref "C33") (pin "1") (pinfunction "1_1") (pintype "passive"))
      (node (ref "R30") (pin "1") (pinfunction "1_1") (pintype "passive"))
      (node (ref "R31") (pin "1") (pinfunction "1_1") (pintype "passive"))
      (node (ref "R32") (pin "2") (pinfunction "2_2") (pintype "passive"))
      (node (ref "U3") (pin "2") (pinfunction "-IN_2") (pintype "input"))
    )
    (net (code "86") (name "Net-(U3A-OUT)") (class "Default")
      (node (ref "C33") (pin "2") (pinfunction "2_2") (pintype "passive"))
      (node (ref "R43") (pin "2") (pinfunction "2_2") (pintype "passive"))
      (node (ref "U3") (pin "1") (pinfunction "OUT_1") (pintype "output"))
    )
    (net (code "87") (name "Net-(U3B--IN)") (class "Default")
      (node (ref "C32") (pin "1") (pinfunction "1_1") (pintype "passive"))
      (node (ref "R27") (pin "1") (pinfunction "1_1") (pintype "passive"))
      (node (ref "R28") (pin "1") (pinfunction "1_1") (pintype "passive"))
      (node (ref "R29") (pin "2") (pinfunction "2_2") (pintype "passive"))
      (node (ref "U3") (pin "6") (pinfunction "-IN_6") (pintype "input"))
    )
    (net (code "88") (name "Net-(U3B-OUT)") (class "Default")
      (node (ref "C32") (pin "2") (pinfunction "2_2") (pintype "passive"))
      (node (ref "R42") (pin "2") (pinfunction "2_2") (pintype "passive"))
      (node (ref "U3") (pin "7") (pinfunction "OUT_7") (pintype "output"))
    )
    (net (code "89") (name "Net-(U3C--IN)") (class "Default")
      (node (ref "C34") (pin "1") (pinfunction "1_1") (pintype "passive"))
      (node (ref "R33") (pin "1") (pinfunction "1_1") (pintype "passive"))
      (node (ref "R34") (pin "1") (pinfunction "1_1") (pintype "passive"))
      (node (ref "R35") (pin "2") (pinfunction "2_2") (pintype "passive"))
      (node (ref "U3") (pin "9") (pinfunction "-IN_9") (pintype "input"))
    )
    (net (code "90") (name "Net-(U3C-OUT)") (class "Default")
      (node (ref "C34") (pin "2") (pinfunction "2_2") (pintype "passive"))
      (node (ref "R40") (pin "2") (pinfunction "2_2") (pintype "passive"))
      (node (ref "U3") (pin "8") (pinfunction "OUT_8") (pintype "output"))
    )
    (net (code "91") (name "Net-(U3D--IN)") (class "Default")
      (node (ref "U3") (pin "13") (pinfunction "-IN_13") (pintype "input"))
      (node (ref "U3") (pin "14") (pinfunction "OUT_14") (pintype "output"))
    )
    (net (code "92") (name "POTS_ADDR_A") (class "Default")
      (node (ref "IC4") (pin "11") (pinfunction "A_11") (pintype "input"))
      (node (ref "U1") (pin "13") (pinfunction "PA7_13") (pintype "bidirectional"))
    )
    (net (code "93") (name "POTS_ADDR_B") (class "Default")
      (node (ref "IC4") (pin "10") (pinfunction "B_10") (pintype "input"))
      (node (ref "U1") (pin "18") (pinfunction "PA8_18") (pintype "bidirectional"))
    )
    (net (code "94") (name "POTS_ADDR_C") (class "Default")
      (node (ref "IC4") (pin "9") (pinfunction "C_9") (pintype "input"))
      (node (ref "U1") (pin "19") (pinfunction "PA9_19") (pintype "bidirectional"))
    )
    (net (code "95") (name "RESET") (class "Default")
      (node (ref "C28") (pin "1") (pinfunction "1_1") (pintype "passive"))
      (node (ref "JP2") (pin "4") (pinfunction "4_4") (pintype "passive"))
      (node (ref "R10") (pin "2") (pinfunction "2_2") (pintype "passive"))
      (node (ref "U1") (pin "4") (pinfunction "NRST_4") (pintype "bidirectional"))
    )
    (net (code "96") (name "SWCLK") (class "Default")
      (node (ref "JP2") (pin "3") (pinfunction "3_3") (pintype "passive"))
      (node (ref "U1") (pin "24") (pinfunction "PA14_24") (pintype "bidirectional"))
    )
    (net (code "97") (name "SWDIO") (class "Default")
      (node (ref "JP2") (pin "2") (pinfunction "2_2") (pintype "passive"))
      (node (ref "U1") (pin "23") (pinfunction "PA13_23") (pintype "bidirectional"))
    )
    (net (code "98") (name "SW_MODE_A") (class "Default")
      (node (ref "SW_A") (pin "3") (pinfunction "3_3") (pintype "passive"))
      (node (ref "SW_A") (pin "4") (pinfunction "4_4") (pintype "passive"))
      (node (ref "U1") (pin "27") (pinfunction "PB4_27") (pintype "bidirectional"))
    )
    (net (code "99") (name "SW_MODE_B") (class "Default")
      (node (ref "SW_B") (pin "3") (pinfunction "3_3") (pintype "passive"))
      (node (ref "SW_B") (pin "4") (pinfunction "4_4") (pintype "passive"))
      (node (ref "U1") (pin "29") (pinfunction "PB6_29") (pintype "bidirectional"))
    )
    (net (code "100") (name "SW_MODE_C") (class "Default")
      (node (ref "SW_C") (pin "3") (pinfunction "3_3") (pintype "passive"))
      (node (ref "SW_C") (pin "4") (pinfunction "4_4") (pintype "passive"))
      (node (ref "U1") (pin "30") (pinfunction "PB7_30") (pintype "bidirectional"))
    )
    (net (code "101") (name "VCC") (class "Default")
      (node (ref "C2") (pin "1") (pinfunction "1_1") (pintype "passive"))
      (node (ref "C31") (pin "1") (pinfunction "1_1") (pintype "passive"))
      (node (ref "C35") (pin "1") (pinfunction "1_1") (pintype "passive"))
      (node (ref "C4") (pin "1") (pinfunction "1_1") (pintype "passive"))
      (node (ref "IC6") (pin "4") (pinfunction "V+_4") (pintype "power_in"))
      (node (ref "L3") (pin "1") (pinfunction "1_1") (pintype "passive"))
      (node (ref "U$1") (pin "1") (pinfunction "P$1_1") (pintype "bidirectional"))
      (node (ref "U3") (pin "4") (pinfunction "V+_4") (pintype "power_in"))
    )
    (net (code "102") (name "VEE") (class "Default")
      (node (ref "C10") (pin "2") (pinfunction "2_2") (pintype "passive"))
      (node (ref "C25") (pin "2") (pinfunction "2_2") (pintype "passive"))
      (node (ref "C9") (pin "2") (pinfunction "2_2") (pintype "passive"))
      (node (ref "L4") (pin "1") (pinfunction "1_1") (pintype "passive"))
      (node (ref "R1") (pin "1") (pinfunction "1_1") (pintype "passive"))
      (node (ref "U$1") (pin "2") (pinfunction "P$2_2") (pintype "bidirectional"))
      (node (ref "U3") (pin "11") (pinfunction "V-_11") (pintype "power_in"))
    )
    (net (code "103") (name "unconnected-(IC4A-X5-Pad5)") (class "Default")
      (node (ref "IC4") (pin "5") (pinfunction "X5_5") (pintype "bidirectional"))
    )
    (net (code "104") (name "unconnected-(IC4A-X7-Pad4)") (class "Default")
      (node (ref "IC4") (pin "4") (pinfunction "X7_4") (pintype "bidirectional"))
    )
    (net (code "105") (name "unconnected-(IC5-LAT-Pad4)") (class "Default")
      (node (ref "IC5") (pin "4") (pinfunction "LAT_4") (pintype "bidirectional"))
    )
    (net (code "106") (name "unconnected-(IC5-OUT0-Pad5)") (class "Default")
      (node (ref "IC5") (pin "5") (pinfunction "OUT0_5") (pintype "bidirectional"))
    )
    (net (code "107") (name "unconnected-(IC5-SOUT-Pad22)") (class "Default")
      (node (ref "IC5") (pin "22") (pinfunction "SOUT_22") (pintype "bidirectional"))
    )
    (net (code "108") (name "unconnected-(J7-2-PadP2)") (class "Default")
      (node (ref "J7") (pin "P2") (pinfunction "2_P2") (pintype "passive"))
    )
    (net (code "109") (name "unconnected-(J8-2-PadP2)") (class "Default")
      (node (ref "J8") (pin "P2") (pinfunction "2_P2") (pintype "passive"))
    )
    (net (code "110") (name "unconnected-(J9-2-PadP2)") (class "Default")
      (node (ref "J9") (pin "P2") (pinfunction "2_P2") (pintype "passive"))
    )
    (net (code "111") (name "unconnected-(J10-2-PadP2)") (class "Default")
      (node (ref "J10") (pin "P2") (pinfunction "2_P2") (pintype "passive"))
    )
    (net (code "112") (name "unconnected-(J11-2-PadP2)") (class "Default")
      (node (ref "J11") (pin "P2") (pinfunction "2_P2") (pintype "passive"))
    )
    (net (code "113") (name "unconnected-(J12-2-PadP2)") (class "Default")
      (node (ref "J12") (pin "P2") (pinfunction "2_P2") (pintype "passive"))
    )
  )
)
